# USB_RS232_Adaper_V1.net
KiCad netlist of a schematic drawn in EAGLE
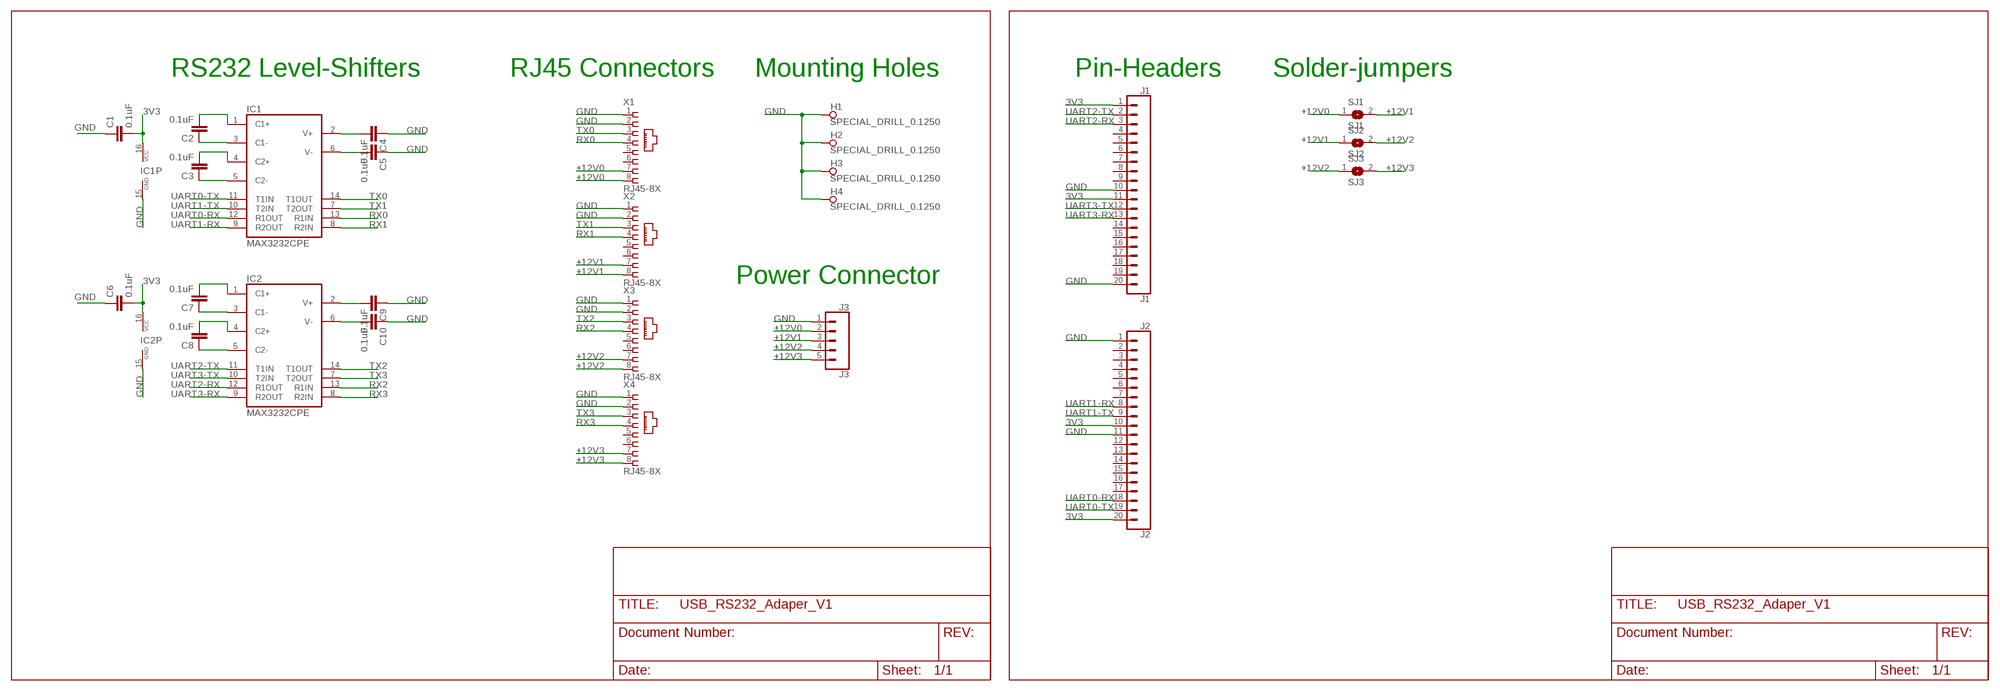
[diagram p0: schematic, sheet 1]

(export (version "E")
  (design (tool "Eeschema 10.0.6"))
  (components
    (comp (ref "C1")
      (value "0.1uF")
      (footprint "eagle-import:CAP-PTH-SMALL-KIT")
      (libsource (lib "eagle-import") (part "0.1UF-KIT-EZ-50V-20%"))
    )
    (comp (ref "C2")
      (value "0.1uF")
      (footprint "eagle-import:CAP-PTH-SMALL-KIT")
      (libsource (lib "eagle-import") (part "0.1UF-KIT-EZ-50V-20%"))
    )
    (comp (ref "C3")
      (value "0.1uF")
      (footprint "eagle-import:CAP-PTH-SMALL-KIT")
      (libsource (lib "eagle-import") (part "0.1UF-KIT-EZ-50V-20%"))
    )
    (comp (ref "C4")
      (value "0.1uF")
      (footprint "eagle-import:CAP-PTH-SMALL-KIT")
      (libsource (lib "eagle-import") (part "0.1UF-KIT-EZ-50V-20%"))
    )
    (comp (ref "C5")
      (value "0.1uF")
      (footprint "eagle-import:CAP-PTH-SMALL-KIT")
      (libsource (lib "eagle-import") (part "0.1UF-KIT-EZ-50V-20%"))
    )
    (comp (ref "C6")
      (value "0.1uF")
      (footprint "eagle-import:CAP-PTH-SMALL-KIT")
      (libsource (lib "eagle-import") (part "0.1UF-KIT-EZ-50V-20%"))
    )
    (comp (ref "C7")
      (value "0.1uF")
      (footprint "eagle-import:CAP-PTH-SMALL-KIT")
      (libsource (lib "eagle-import") (part "0.1UF-KIT-EZ-50V-20%"))
    )
    (comp (ref "C8")
      (value "0.1uF")
      (footprint "eagle-import:CAP-PTH-SMALL-KIT")
      (libsource (lib "eagle-import") (part "0.1UF-KIT-EZ-50V-20%"))
    )
    (comp (ref "C9")
      (value "0.1uF")
      (footprint "eagle-import:CAP-PTH-SMALL-KIT")
      (libsource (lib "eagle-import") (part "0.1UF-KIT-EZ-50V-20%"))
    )
    (comp (ref "C10")
      (value "0.1uF")
      (footprint "eagle-import:CAP-PTH-SMALL-KIT")
      (libsource (lib "eagle-import") (part "0.1UF-KIT-EZ-50V-20%"))
    )
    (comp (ref "H1")
      (value "SPECIAL_DRILL_0.1250")
      (footprint "eagle-import:PAD_0.1250")
      (libsource (lib "eagle-import") (part "SPECIAL_DRILL_0.1250"))
    )
    (comp (ref "H2")
      (value "SPECIAL_DRILL_0.1250")
      (footprint "eagle-import:PAD_0.1250")
      (libsource (lib "eagle-import") (part "SPECIAL_DRILL_0.1250"))
    )
    (comp (ref "H3")
      (value "SPECIAL_DRILL_0.1250")
      (footprint "eagle-import:PAD_0.1250")
      (libsource (lib "eagle-import") (part "SPECIAL_DRILL_0.1250"))
    )
    (comp (ref "H4")
      (value "SPECIAL_DRILL_0.1250")
      (footprint "eagle-import:PAD_0.1250")
      (libsource (lib "eagle-import") (part "SPECIAL_DRILL_0.1250"))
    )
    (comp (ref "IC1")
      (value "MAX3232CPE")
      (footprint "eagle-import:DIL16")
      (fields (field (name "MF") "MAXIM") (field (name "MPN") "MAX3232CPE+"))
      (libsource (lib "eagle-import") (part "MAX3232PEC"))
    )
    (comp (ref "IC2")
      (value "MAX3232CPE")
      (footprint "eagle-import:DIL16")
      (fields (field (name "MF") "MAXIM") (field (name "MPN") "MAX3232CPE+"))
      (libsource (lib "eagle-import") (part "MAX3232PEC"))
    )
    (comp (ref "J1")
      (value "J1")
      (footprint "eagle-import:1X20")
      (libsource (lib "eagle-import") (part "CONN_20"))
    )
    (comp (ref "J2")
      (value "J2")
      (footprint "eagle-import:1X20")
      (libsource (lib "eagle-import") (part "CONN_20"))
    )
    (comp (ref "J3")
      (value "J3")
      (footprint "eagle-import:1X05")
      (libsource (lib "eagle-import") (part "CONN_05"))
    )
    (comp (ref "SJ1")
      (value "SJ1")
      (footprint "eagle-import:SJ")
      (libsource (lib "eagle-import") (part "SJ"))
    )
    (comp (ref "SJ2")
      (value "SJ2")
      (footprint "eagle-import:SJ")
      (libsource (lib "eagle-import") (part "SJ"))
    )
    (comp (ref "SJ3")
      (value "SJ3")
      (footprint "eagle-import:SJ")
      (libsource (lib "eagle-import") (part "SJ"))
    )
    (comp (ref "X1")
      (value "RJ45-8X")
      (footprint "eagle-import:RJ45-NO-SHIELD")
      (libsource (lib "eagle-import") (part "RJ45-8X"))
    )
    (comp (ref "X2")
      (value "RJ45-8X")
      (footprint "eagle-import:RJ45-NO-SHIELD")
      (libsource (lib "eagle-import") (part "RJ45-8X"))
    )
    (comp (ref "X3")
      (value "RJ45-8X")
      (footprint "eagle-import:RJ45-NO-SHIELD")
      (libsource (lib "eagle-import") (part "RJ45-8X"))
    )
    (comp (ref "X4")
      (value "RJ45-8X")
      (footprint "eagle-import:RJ45-NO-SHIELD")
      (libsource (lib "eagle-import") (part "RJ45-8X"))
    )
  )
  (nets
    (net (code "1") (name "/+12V0") (class "Default")
      (node (ref "J3") (pin "2") (pinfunction "2_2") (pintype "passive"))
      (node (ref "SJ1") (pin "1") (pinfunction "1_1") (pintype "passive"))
      (node (ref "X1") (pin "7") (pinfunction "7_7") (pintype "passive"))
      (node (ref "X1") (pin "8") (pinfunction "8_8") (pintype "passive"))
    )
    (net (code "2") (name "/+12V1") (class "Default")
      (node (ref "J3") (pin "3") (pinfunction "3_3") (pintype "passive"))
      (node (ref "SJ1") (pin "2") (pinfunction "2_2") (pintype "passive"))
      (node (ref "SJ2") (pin "1") (pinfunction "1_1") (pintype "passive"))
      (node (ref "X2") (pin "7") (pinfunction "7_7") (pintype "passive"))
      (node (ref "X2") (pin "8") (pinfunction "8_8") (pintype "passive"))
    )
    (net (code "3") (name "/+12V2") (class "Default")
      (node (ref "J3") (pin "4") (pinfunction "4_4") (pintype "passive"))
      (node (ref "SJ2") (pin "2") (pinfunction "2_2") (pintype "passive"))
      (node (ref "SJ3") (pin "1") (pinfunction "1_1") (pintype "passive"))
      (node (ref "X3") (pin "7") (pinfunction "7_7") (pintype "passive"))
      (node (ref "X3") (pin "8") (pinfunction "8_8") (pintype "passive"))
    )
    (net (code "4") (name "/+12V3") (class "Default")
      (node (ref "J3") (pin "5") (pinfunction "5_5") (pintype "passive"))
      (node (ref "SJ3") (pin "2") (pinfunction "2_2") (pintype "passive"))
      (node (ref "X4") (pin "7") (pinfunction "7_7") (pintype "passive"))
      (node (ref "X4") (pin "8") (pinfunction "8_8") (pintype "passive"))
    )
    (net (code "5") (name "/3V3") (class "Default")
      (node (ref "C1") (pin "2") (pinfunction "2_2") (pintype "passive"))
      (node (ref "C6") (pin "2") (pinfunction "2_2") (pintype "passive"))
      (node (ref "IC1") (pin "16") (pinfunction "VCC_16") (pintype "power_in"))
      (node (ref "IC2") (pin "16") (pinfunction "VCC_16") (pintype "power_in"))
      (node (ref "J1") (pin "1") (pinfunction "1_1") (pintype "passive"))
      (node (ref "J1") (pin "11") (pinfunction "11_11") (pintype "passive"))
      (node (ref "J2") (pin "10") (pinfunction "10_10") (pintype "passive"))
      (node (ref "J2") (pin "20") (pinfunction "20_20") (pintype "passive"))
    )
    (net (code "6") (name "/GND") (class "Default")
      (node (ref "C1") (pin "1") (pinfunction "1_1") (pintype "passive"))
      (node (ref "C10") (pin "1") (pinfunction "1_1") (pintype "passive"))
      (node (ref "C4") (pin "1") (pinfunction "1_1") (pintype "passive"))
      (node (ref "C5") (pin "1") (pinfunction "1_1") (pintype "passive"))
      (node (ref "C6") (pin "1") (pinfunction "1_1") (pintype "passive"))
      (node (ref "C9") (pin "1") (pinfunction "1_1") (pintype "passive"))
      (node (ref "H1") (pin "1") (pinfunction "1_1") (pintype "passive"))
      (node (ref "H2") (pin "1") (pinfunction "1_1") (pintype "passive"))
      (node (ref "H3") (pin "1") (pinfunction "1_1") (pintype "passive"))
      (node (ref "H4") (pin "1") (pinfunction "1_1") (pintype "passive"))
      (node (ref "IC1") (pin "15") (pinfunction "GND_15") (pintype "power_in"))
      (node (ref "IC2") (pin "15") (pinfunction "GND_15") (pintype "power_in"))
      (node (ref "J1") (pin "10") (pinfunction "10_10") (pintype "passive"))
      (node (ref "J1") (pin "20") (pinfunction "20_20") (pintype "passive"))
      (node (ref "J2") (pin "1") (pinfunction "1_1") (pintype "passive"))
      (node (ref "J2") (pin "11") (pinfunction "11_11") (pintype "passive"))
      (node (ref "J3") (pin "1") (pinfunction "1_1") (pintype "passive"))
      (node (ref "X1") (pin "1") (pinfunction "1_1") (pintype "passive"))
      (node (ref "X1") (pin "2") (pinfunction "2_2") (pintype "passive"))
      (node (ref "X2") (pin "1") (pinfunction "1_1") (pintype "passive"))
      (node (ref "X2") (pin "2") (pinfunction "2_2") (pintype "passive"))
      (node (ref "X3") (pin "1") (pinfunction "1_1") (pintype "passive"))
      (node (ref "X3") (pin "2") (pinfunction "2_2") (pintype "passive"))
      (node (ref "X4") (pin "1") (pinfunction "1_1") (pintype "passive"))
      (node (ref "X4") (pin "2") (pinfunction "2_2") (pintype "passive"))
    )
    (net (code "7") (name "/RX0") (class "Default")
      (node (ref "IC1") (pin "13") (pinfunction "R1IN_13") (pintype "input"))
      (node (ref "X1") (pin "4") (pinfunction "4_4") (pintype "passive"))
    )
    (net (code "8") (name "/RX1") (class "Default")
      (node (ref "IC1") (pin "8") (pinfunction "R2IN_8") (pintype "input"))
      (node (ref "X2") (pin "4") (pinfunction "4_4") (pintype "passive"))
    )
    (net (code "9") (name "/RX2") (class "Default")
      (node (ref "IC2") (pin "13") (pinfunction "R1IN_13") (pintype "input"))
      (node (ref "X3") (pin "4") (pinfunction "4_4") (pintype "passive"))
    )
    (net (code "10") (name "/RX3") (class "Default")
      (node (ref "IC2") (pin "8") (pinfunction "R2IN_8") (pintype "input"))
      (node (ref "X4") (pin "4") (pinfunction "4_4") (pintype "passive"))
    )
    (net (code "11") (name "/TX0") (class "Default")
      (node (ref "IC1") (pin "14") (pinfunction "T1OUT_14") (pintype "output"))
      (node (ref "X1") (pin "3") (pinfunction "3_3") (pintype "passive"))
    )
    (net (code "12") (name "/TX1") (class "Default")
      (node (ref "IC1") (pin "7") (pinfunction "T2OUT_7") (pintype "output"))
      (node (ref "X2") (pin "3") (pinfunction "3_3") (pintype "passive"))
    )
    (net (code "13") (name "/TX2") (class "Default")
      (node (ref "IC2") (pin "14") (pinfunction "T1OUT_14") (pintype "output"))
      (node (ref "X3") (pin "3") (pinfunction "3_3") (pintype "passive"))
    )
    (net (code "14") (name "/TX3") (class "Default")
      (node (ref "IC2") (pin "7") (pinfunction "T2OUT_7") (pintype "output"))
      (node (ref "X4") (pin "3") (pinfunction "3_3") (pintype "passive"))
    )
    (net (code "15") (name "/UART0-RX") (class "Default")
      (node (ref "IC1") (pin "12") (pinfunction "R1OUT_12") (pintype "output"))
      (node (ref "J2") (pin "18") (pinfunction "18_18") (pintype "passive"))
    )
    (net (code "16") (name "/UART0-TX") (class "Default")
      (node (ref "IC1") (pin "11") (pinfunction "T1IN_11") (pintype "input"))
      (node (ref "J2") (pin "19") (pinfunction "19_19") (pintype "passive"))
    )
    (net (code "17") (name "/UART1-RX") (class "Default")
      (node (ref "IC1") (pin "9") (pinfunction "R2OUT_9") (pintype "output"))
      (node (ref "J2") (pin "8") (pinfunction "8_8") (pintype "passive"))
    )
    (net (code "18") (name "/UART1-TX") (class "Default")
      (node (ref "IC1") (pin "10") (pinfunction "T2IN_10") (pintype "input"))
      (node (ref "J2") (pin "9") (pinfunction "9_9") (pintype "passive"))
    )
    (net (code "19") (name "/UART2-RX") (class "Default")
      (node (ref "IC2") (pin "12") (pinfunction "R1OUT_12") (pintype "output"))
      (node (ref "J1") (pin "3") (pinfunction "3_3") (pintype "passive"))
    )
    (net (code "20") (name "/UART2-TX") (class "Default")
      (node (ref "IC2") (pin "11") (pinfunction "T1IN_11") (pintype "input"))
      (node (ref "J1") (pin "2") (pinfunction "2_2") (pintype "passive"))
    )
    (net (code "21") (name "/UART3-RX") (class "Default")
      (node (ref "IC2") (pin "9") (pinfunction "R2OUT_9") (pintype "output"))
      (node (ref "J1") (pin "13") (pinfunction "13_13") (pintype "passive"))
    )
    (net (code "22") (name "/UART3-TX") (class "Default")
      (node (ref "IC2") (pin "10") (pinfunction "T2IN_10") (pintype "input"))
      (node (ref "J1") (pin "12") (pinfunction "12_12") (pintype "passive"))
    )
    (net (code "23") (name "Net-(IC1A-C1+)") (class "Default")
      (node (ref "C2") (pin "2") (pinfunction "2_2") (pintype "passive"))
      (node (ref "IC1") (pin "1") (pinfunction "C1+_1") (pintype "bidirectional"))
    )
    (net (code "24") (name "Net-(IC1A-C1-)") (class "Default")
      (node (ref "C2") (pin "1") (pinfunction "1_1") (pintype "passive"))
      (node (ref "IC1") (pin "3") (pinfunction "C1-_3") (pintype "bidirectional"))
    )
    (net (code "25") (name "Net-(IC1A-C2+)") (class "Default")
      (node (ref "C3") (pin "2") (pinfunction "2_2") (pintype "passive"))
      (node (ref "IC1") (pin "4") (pinfunction "C2+_4") (pintype "bidirectional"))
    )
    (net (code "26") (name "Net-(IC1A-C2-)") (class "Default")
      (node (ref "C3") (pin "1") (pinfunction "1_1") (pintype "passive"))
      (node (ref "IC1") (pin "5") (pinfunction "C2-_5") (pintype "bidirectional"))
    )
    (net (code "27") (name "Net-(IC1A-V+)") (class "Default")
      (node (ref "C4") (pin "2") (pinfunction "2_2") (pintype "passive"))
      (node (ref "IC1") (pin "2") (pinfunction "V+_2") (pintype "bidirectional"))
    )
    (net (code "28") (name "Net-(IC1A-V-)") (class "Default")
      (node (ref "C5") (pin "2") (pinfunction "2_2") (pintype "passive"))
      (node (ref "IC1") (pin "6") (pinfunction "V-_6") (pintype "bidirectional"))
    )
    (net (code "29") (name "Net-(IC2A-C1+)") (class "Default")
      (node (ref "C7") (pin "2") (pinfunction "2_2") (pintype "passive"))
      (node (ref "IC2") (pin "1") (pinfunction "C1+_1") (pintype "bidirectional"))
    )
    (net (code "30") (name "Net-(IC2A-C1-)") (class "Default")
      (node (ref "C7") (pin "1") (pinfunction "1_1") (pintype "passive"))
      (node (ref "IC2") (pin "3") (pinfunction "C1-_3") (pintype "bidirectional"))
    )
    (net (code "31") (name "Net-(IC2A-C2+)") (class "Default")
      (node (ref "C8") (pin "2") (pinfunction "2_2") (pintype "passive"))
      (node (ref "IC2") (pin "4") (pinfunction "C2+_4") (pintype "bidirectional"))
    )
    (net (code "32") (name "Net-(IC2A-C2-)") (class "Default")
      (node (ref "C8") (pin "1") (pinfunction "1_1") (pintype "passive"))
      (node (ref "IC2") (pin "5") (pinfunction "C2-_5") (pintype "bidirectional"))
    )
    (net (code "33") (name "Net-(IC2A-V+)") (class "Default")
      (node (ref "C9") (pin "2") (pinfunction "2_2") (pintype "passive"))
      (node (ref "IC2") (pin "2") (pinfunction "V+_2") (pintype "bidirectional"))
    )
    (net (code "34") (name "Net-(IC2A-V-)") (class "Default")
      (node (ref "C10") (pin "2") (pinfunction "2_2") (pintype "passive"))
      (node (ref "IC2") (pin "6") (pinfunction "V-_6") (pintype "bidirectional"))
    )
    (net (code "35") (name "unconnected-(J1-Pad4)") (class "Default")
      (node (ref "J1") (pin "4") (pinfunction "4_4") (pintype "passive"))
    )
    (net (code "36") (name "unconnected-(J1-Pad5)") (class "Default")
      (node (ref "J1") (pin "5") (pinfunction "5_5") (pintype "passive"))
    )
    (net (code "37") (name "unconnected-(J1-Pad6)") (class "Default")
      (node (ref "J1") (pin "6") (pinfunction "6_6") (pintype "passive"))
    )
    (net (code "38") (name "unconnected-(J1-Pad7)") (class "Default")
      (node (ref "J1") (pin "7") (pinfunction "7_7") (pintype "passive"))
    )
    (net (code "39") (name "unconnected-(J1-Pad8)") (class "Default")
      (node (ref "J1") (pin "8") (pinfunction "8_8") (pintype "passive"))
    )
    (net (code "40") (name "unconnected-(J1-Pad9)") (class "Default")
      (node (ref "J1") (pin "9") (pinfunction "9_9") (pintype "passive"))
    )
    (net (code "41") (name "unconnected-(J1-Pad14)") (class "Default")
      (node (ref "J1") (pin "14") (pinfunction "14_14") (pintype "passive"))
    )
    (net (code "42") (name "unconnected-(J1-Pad15)") (class "Default")
      (node (ref "J1") (pin "15") (pinfunction "15_15") (pintype "passive"))
    )
    (net (code "43") (name "unconnected-(J1-Pad16)") (class "Default")
      (node (ref "J1") (pin "16") (pinfunction "16_16") (pintype "passive"))
    )
    (net (code "44") (name "unconnected-(J1-Pad17)") (class "Default")
      (node (ref "J1") (pin "17") (pinfunction "17_17") (pintype "passive"))
    )
    (net (code "45") (name "unconnected-(J1-Pad18)") (class "Default")
      (node (ref "J1") (pin "18") (pinfunction "18_18") (pintype "passive"))
    )
    (net (code "46") (name "unconnected-(J1-Pad19)") (class "Default")
      (node (ref "J1") (pin "19") (pinfunction "19_19") (pintype "passive"))
    )
    (net (code "47") (name "unconnected-(J2-Pad2)") (class "Default")
      (node (ref "J2") (pin "2") (pinfunction "2_2") (pintype "passive"))
    )
    (net (code "48") (name "unconnected-(J2-Pad3)") (class "Default")
      (node (ref "J2") (pin "3") (pinfunction "3_3") (pintype "passive"))
    )
    (net (code "49") (name "unconnected-(J2-Pad4)") (class "Default")
      (node (ref "J2") (pin "4") (pinfunction "4_4") (pintype "passive"))
    )
    (net (code "50") (name "unconnected-(J2-Pad5)") (class "Default")
      (node (ref "J2") (pin "5") (pinfunction "5_5") (pintype "passive"))
    )
    (net (code "51") (name "unconnected-(J2-Pad6)") (class "Default")
      (node (ref "J2") (pin "6") (pinfunction "6_6") (pintype "passive"))
    )
    (net (code "52") (name "unconnected-(J2-Pad7)") (class "Default")
      (node (ref "J2") (pin "7") (pinfunction "7_7") (pintype "passive"))
    )
    (net (code "53") (name "unconnected-(J2-Pad12)") (class "Default")
      (node (ref "J2") (pin "12") (pinfunction "12_12") (pintype "passive"))
    )
    (net (code "54") (name "unconnected-(J2-Pad13)") (class "Default")
      (node (ref "J2") (pin "13") (pinfunction "13_13") (pintype "passive"))
    )
    (net (code "55") (name "unconnected-(J2-Pad14)") (class "Default")
      (node (ref "J2") (pin "14") (pinfunction "14_14") (pintype "passive"))
    )
    (net (code "56") (name "unconnected-(J2-Pad15)") (class "Default")
      (node (ref "J2") (pin "15") (pinfunction "15_15") (pintype "passive"))
    )
    (net (code "57") (name "unconnected-(J2-Pad16)") (class "Default")
      (node (ref "J2") (pin "16") (pinfunction "16_16") (pintype "passive"))
    )
    (net (code "58") (name "unconnected-(J2-Pad17)") (class "Default")
      (node (ref "J2") (pin "17") (pinfunction "17_17") (pintype "passive"))
    )
    (net (code "59") (name "unconnected-(X1-Pad5)") (class "Default")
      (node (ref "X1") (pin "5") (pinfunction "5_5") (pintype "passive"))
    )
    (net (code "60") (name "unconnected-(X1-Pad6)") (class "Default")
      (node (ref "X1") (pin "6") (pinfunction "6_6") (pintype "passive"))
    )
    (net (code "61") (name "unconnected-(X2-Pad5)") (class "Default")
      (node (ref "X2") (pin "5") (pinfunction "5_5") (pintype "passive"))
    )
    (net (code "62") (name "unconnected-(X2-Pad6)") (class "Default")
      (node (ref "X2") (pin "6") (pinfunction "6_6") (pintype "passive"))
    )
    (net (code "63") (name "unconnected-(X3-Pad5)") (class "Default")
      (node (ref "X3") (pin "5") (pinfunction "5_5") (pintype "passive"))
    )
    (net (code "64") (name "unconnected-(X3-Pad6)") (class "Default")
      (node (ref "X3") (pin "6") (pinfunction "6_6") (pintype "passive"))
    )
    (net (code "65") (name "unconnected-(X4-Pad5)") (class "Default")
      (node (ref "X4") (pin "5") (pinfunction "5_5") (pintype "passive"))
    )
    (net (code "66") (name "unconnected-(X4-Pad6)") (class "Default")
      (node (ref "X4") (pin "6") (pinfunction "6_6") (pintype "passive"))
    )
  )
)
